# S1.net
KiCad netlist of a schematic drawn in EasyEDA Pro
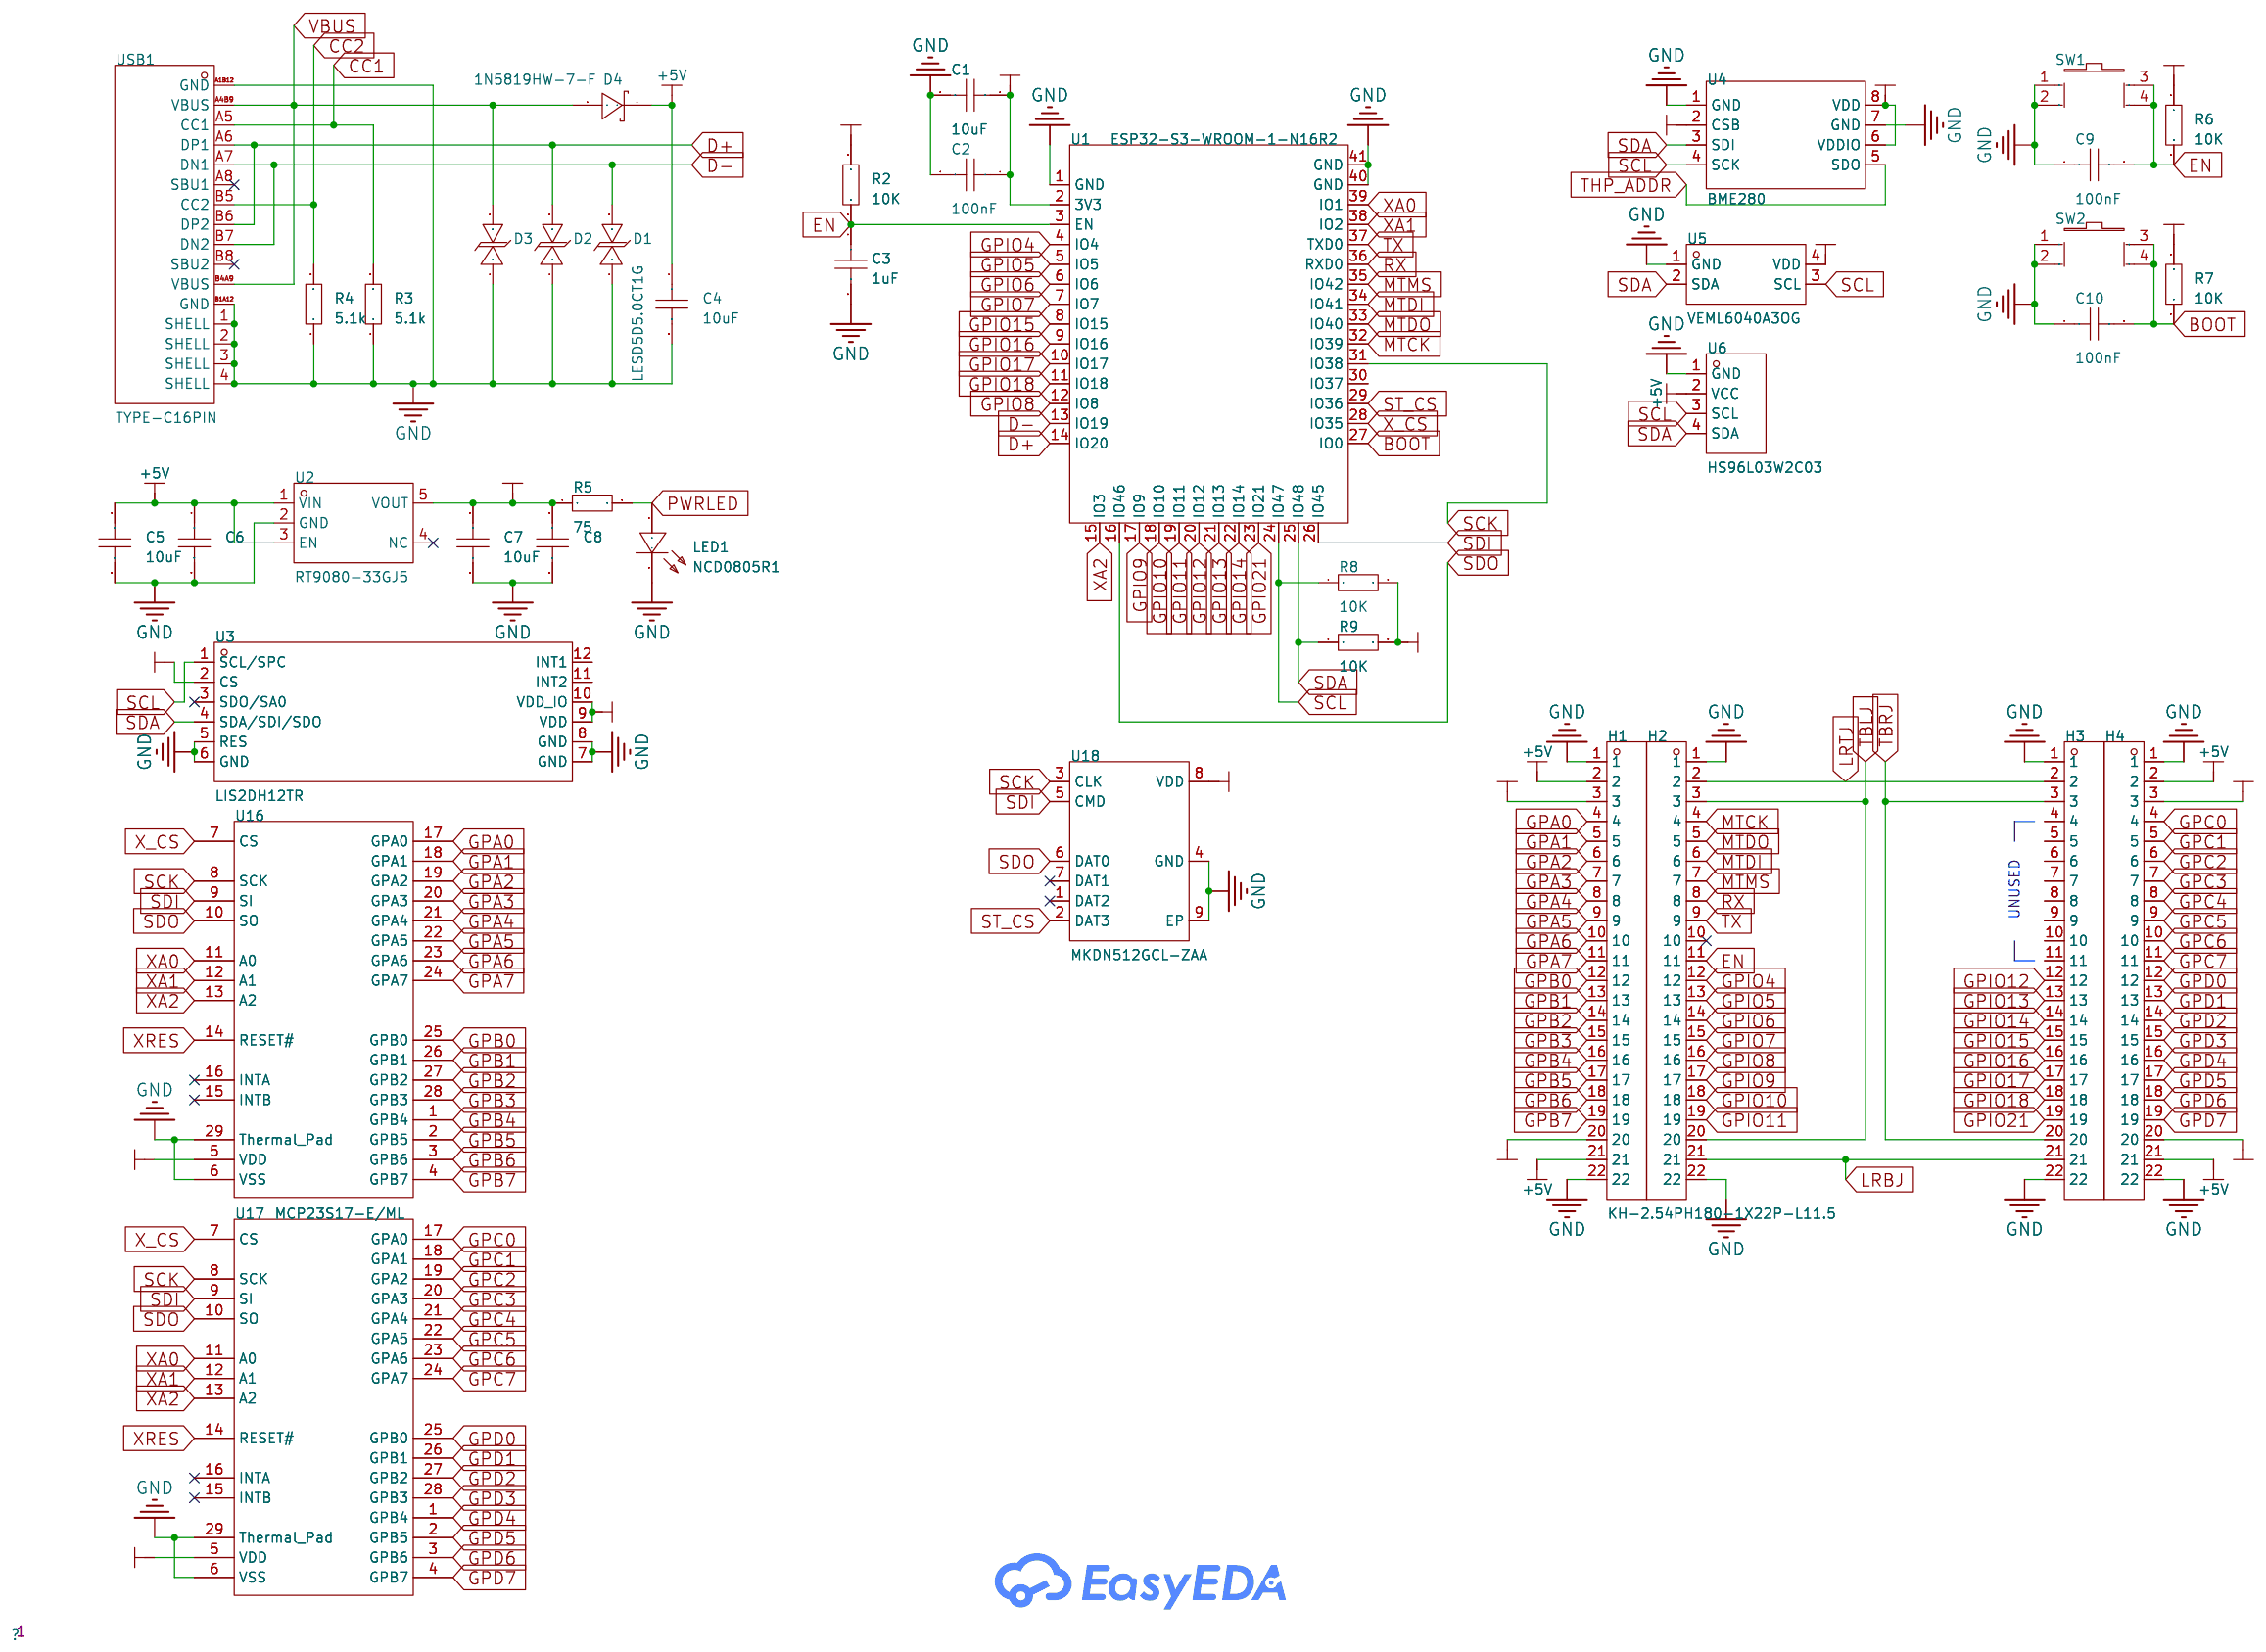
[diagram p0: schematic sheet]

(export (version "E")
  (design (tool "Eeschema 10.0.6"))
  (components
    (comp (ref "C1")
      (value "10uF")
      (footprint "easyedapro:C0603")
      (libsource (lib "easyedapro") (part "CAP"))
    )
    (comp (ref "C2")
      (value "100nF")
      (footprint "easyedapro:C0603")
      (libsource (lib "easyedapro") (part "CAP"))
    )
    (comp (ref "C3") (value "1uF") (footprint "easyedapro:C0603") (libsource (lib "easyedapro") (part "CAP")))
    (comp (ref "C4")
      (value "10uF")
      (footprint "easyedapro:C0603")
      (libsource (lib "easyedapro") (part "CAP"))
    )
    (comp (ref "C5")
      (value "10uF")
      (footprint "easyedapro:C0603")
      (libsource (lib "easyedapro") (part "CAP"))
    )
    (comp (ref "C6")
      (value "100nF")
      (footprint "easyedapro:C0603")
      (libsource (lib "easyedapro") (part "CAP"))
    )
    (comp (ref "C7")
      (value "10uF")
      (footprint "easyedapro:C0603")
      (libsource (lib "easyedapro") (part "CAP"))
    )
    (comp (ref "C8")
      (value "100nF")
      (footprint "easyedapro:C0603")
      (libsource (lib "easyedapro") (part "CAP"))
    )
    (comp (ref "C9")
      (value "100nF")
      (footprint "easyedapro:C0603")
      (libsource (lib "easyedapro") (part "CAP"))
    )
    (comp (ref "C10")
      (value "100nF")
      (footprint "easyedapro:C0603")
      (libsource (lib "easyedapro") (part "CAP"))
    )
    (comp (ref "D1")
      (value "LESD5D5.0CT1G")
      (footprint "easyedapro:SOD-523_L1.2-W0.8-LS1.6-BI")
      (fields (field (name "Manufacturer") "UMW(友台半导体)"))
      (libsource (lib "easyedapro") (part "LESD5D5.0CT1G_C5199850"))
    )
    (comp (ref "D2")
      (value "LESD5D5.0CT1G")
      (footprint "easyedapro:SOD-523_L1.2-W0.8-LS1.6-BI")
      (fields (field (name "Manufacturer") "UMW(友台半导体)"))
      (libsource (lib "easyedapro") (part "LESD5D5.0CT1G_C5199850"))
    )
    (comp (ref "D3")
      (value "LESD5D5.0CT1G")
      (footprint "easyedapro:SOD-523_L1.2-W0.8-LS1.6-BI")
      (fields (field (name "Manufacturer") "UMW(友台半导体)"))
      (libsource (lib "easyedapro") (part "LESD5D5.0CT1G_C5199850"))
    )
    (comp (ref "D4")
      (value "1N5819HW-7-F")
      (footprint "easyedapro:SOD-123_L2.7-W1.6-LS3.7-RD")
      (fields (field (name "Manufacturer") "DIODES(美台)"))
      (libsource (lib "easyedapro") (part "1N5819HW-7-F"))
    )
    (comp (ref "H1")
      (value "KH-2.54PH180-1X22P-L11.5")
      (footprint "easyedapro:HDR-TH_22P-P2.54-V-M")
      (description "Pin Structure:1x22P Pitch:2.54mm Number of Rows:Single Row")
      (fields (field (name "Manufacturer") "kinghelm(金航标)"))
      (libsource (lib "easyedapro") (part "KH-2.54PH180-1X22P-L11.5"))
    )
    (comp (ref "H2")
      (value "KH-2.54PH180-1X22P-L11.5")
      (footprint "easyedapro:HDR-TH_22P-P2.54-V-M")
      (description "Pin Structure:1x22P Pitch:2.54mm Number of Rows:Single Row")
      (fields (field (name "Manufacturer") "kinghelm(金航标)"))
      (libsource (lib "easyedapro") (part "KH-2.54PH180-1X22P-L11.5"))
    )
    (comp (ref "H3")
      (value "KH-2.54PH180-1X22P-L11.5")
      (footprint "easyedapro:HDR-TH_22P-P2.54-V-M")
      (description "Pin Structure:1x22P Pitch:2.54mm Number of Rows:Single Row")
      (fields (field (name "Manufacturer") "kinghelm(金航标)"))
      (libsource (lib "easyedapro") (part "KH-2.54PH180-1X22P-L11.5"))
    )
    (comp (ref "H4")
      (value "KH-2.54PH180-1X22P-L11.5")
      (footprint "easyedapro:HDR-TH_22P-P2.54-V-M")
      (description "Pin Structure:1x22P Pitch:2.54mm Number of Rows:Single Row")
      (fields (field (name "Manufacturer") "kinghelm(金航标)"))
      (libsource (lib "easyedapro") (part "KH-2.54PH180-1X22P-L11.5"))
    )
    (comp (ref "LED1")
      (value "NCD0805R1")
      (footprint "easyedapro:LED0805-R-RD")
      (fields (field (name "Manufacturer") "国星光电"))
      (libsource (lib "easyedapro") (part "FC-2012HRK-620D"))
    )
    (comp (ref "R2") (value "10K") (footprint "easyedapro:R0603") (libsource (lib "easyedapro") (part "Res")))
    (comp (ref "R3")
      (value "5.1k")
      (footprint "easyedapro:R0603")
      (libsource (lib "easyedapro") (part "Res"))
    )
    (comp (ref "R4")
      (value "5.1k")
      (footprint "easyedapro:R0603")
      (libsource (lib "easyedapro") (part "Res"))
    )
    (comp (ref "R5") (value "75") (footprint "easyedapro:R0603") (libsource (lib "easyedapro") (part "Res")))
    (comp (ref "R6") (value "10K") (footprint "easyedapro:R0603") (libsource (lib "easyedapro") (part "Res")))
    (comp (ref "R7") (value "10K") (footprint "easyedapro:R0603") (libsource (lib "easyedapro") (part "Res")))
    (comp (ref "R8") (value "10K") (footprint "easyedapro:R0603") (libsource (lib "easyedapro") (part "Res")))
    (comp (ref "R9") (value "10K") (footprint "easyedapro:R0603") (libsource (lib "easyedapro") (part "Res")))
    (comp (ref "SW1")
      (value "PTS810SJG250SMTRLFS")
      (footprint "easyedapro:SW-SMD_4P_PTS810SJM250SMTRLFS")
      (fields (field (name "Manufacturer") "C&K"))
      (libsource (lib "easyedapro") (part "PTS810SJG250SMTRLFS"))
    )
    (comp (ref "SW2")
      (value "PTS810SJG250SMTRLFS")
      (footprint "easyedapro:SW-SMD_4P_PTS810SJM250SMTRLFS")
      (fields (field (name "Manufacturer") "C&K"))
      (libsource (lib "easyedapro") (part "PTS810SJG250SMTRLFS"))
    )
    (comp (ref "U1")
      (value "ESP32-S3-WROOM-1-N16R2")
      (footprint "easyedapro:WIRELM-SMD_ESP32-S3-WROOM-1")
      (fields (field (name "Manufacturer") "ESPRESSIF(乐鑫)"))
      (libsource (lib "easyedapro") (part "ESP32-S3-WROOM-1(N16R2)"))
    )
    (comp (ref "U2")
      (value "RT9080-33GJ5")
      (footprint "easyedapro:TSOT-23-5_L2.9-W1.6-P0.95-LS2.8-BL")
      (description "+3V3")
      (fields (field (name "Manufacturer") "RICHTEK(立锜)"))
      (libsource (lib "easyedapro") (part "RT9080-33GJ5"))
    )
    (comp (ref "U3")
      (value "LIS2DH12TR")
      (footprint "easyedapro:LGA-12_L2.0-W2.0-P0.50-BL")
      (fields (field (name "Manufacturer") "ST(意法半导体)"))
      (libsource (lib "easyedapro") (part "LIS2DH12TR"))
    )
    (comp (ref "U4")
      (value "BME280")
      (footprint "easyedapro:LGA-8_BME280_BL")
      (description "Voltage - Supply:1.71V~3.6V Voltage - Supply:1.71V~3.6V")
      (fields (field (name "Manufacturer") "Bosch(博世)"))
      (libsource (lib "easyedapro") (part "BME280"))
    )
    (comp (ref "U5")
      (value "VEML6040A3OG")
      (footprint "easyedapro:SENSOR_SMD_VEML6040A3OG")
      (fields (field (name "Manufacturer") "VISHAY(威世)"))
      (libsource (lib "easyedapro") (part "VEML6040A3OG"))
    )
    (comp (ref "U6")
      (value "HS96L03W2C03")
      (footprint "easyedapro:OLED-TH_L27.8-W27.2-P2.54_C9900033791")
      (fields (field (name "Manufacturer") "HS(汉昇)"))
      (libsource (lib "easyedapro") (part "HS96L03W2C03"))
    )
    (comp (ref "U16")
      (value "MCP23S17-E/ML")
      (footprint "easyedapro:QFN-28_L6.0-W6.0-P0.65-BL-EP")
      (fields (field (name "Manufacturer") "MICROCHIP(美国微芯)"))
      (libsource (lib "easyedapro") (part "MCP23S17-E/ML"))
    )
    (comp (ref "U17")
      (value "MCP23S17-E/ML")
      (footprint "easyedapro:QFN-28_L6.0-W6.0-P0.65-BL-EP")
      (fields (field (name "Manufacturer") "MICROCHIP(美国微芯)"))
      (libsource (lib "easyedapro") (part "MCP23S17-E/ML"))
    )
    (comp (ref "U18")
      (value "MKDN512GCL-ZAA")
      (footprint "easyedapro:LGA-16_L12.5-W9.0-P1.27-TL-EP")
      (fields (field (name "Manufacturer") "MK(米客方德)"))
      (libsource (lib "easyedapro") (part "MKDN512GCL-ZAA"))
    )
    (comp (ref "USB1")
      (value "TYPE-C16PIN")
      (footprint "easyedapro:USB-C-SMD_TYPE-C16PIN")
      (fields (field (name "Manufacturer") "SHOU HAN(首韩)"))
      (libsource (lib "easyedapro") (part "TYPE-C16PIN"))
    )
  )
  (nets
    (net (code "1") (name "+3V3") (class "Default")
      (node (ref "C1") (pin "1") (pinfunction "1_1") (pintype "input"))
      (node (ref "C2") (pin "1") (pinfunction "1_1") (pintype "input"))
      (node (ref "C7") (pin "1") (pinfunction "1_1") (pintype "input"))
      (node (ref "C8") (pin "1") (pinfunction "1_1") (pintype "input"))
      (node (ref "H1") (pin "20") (pinfunction "20_20") (pintype "unspecified"))
      (node (ref "H1") (pin "3") (pinfunction "3_3") (pintype "unspecified"))
      (node (ref "H4") (pin "20") (pinfunction "20_20") (pintype "unspecified"))
      (node (ref "H4") (pin "3") (pinfunction "3_3") (pintype "unspecified"))
      (node (ref "R2") (pin "2") (pinfunction "2_2") (pintype "input"))
      (node (ref "R5") (pin "1") (pinfunction "1_1") (pintype "input"))
      (node (ref "R6") (pin "1") (pinfunction "1_1") (pintype "input"))
      (node (ref "R7") (pin "2") (pinfunction "2_2") (pintype "input"))
      (node (ref "R8") (pin "2") (pinfunction "2_2") (pintype "input"))
      (node (ref "R9") (pin "2") (pinfunction "2_2") (pintype "input"))
      (node (ref "U1") (pin "2") (pinfunction "3V3_2") (pintype "unspecified"))
      (node (ref "U16") (pin "5") (pinfunction "VDD_5") (pintype "input"))
      (node (ref "U17") (pin "5") (pinfunction "VDD_5") (pintype "input"))
      (node (ref "U18") (pin "8") (pinfunction "VDD_8") (pintype "unspecified"))
      (node (ref "U2") (pin "5") (pinfunction "VOUT_5") (pintype "unspecified"))
      (node (ref "U3") (pin "10") (pinfunction "VDD_IO_10") (pintype "unspecified"))
      (node (ref "U3") (pin "2") (pinfunction "CS_2") (pintype "unspecified"))
      (node (ref "U3") (pin "9") (pinfunction "VDD_9") (pintype "unspecified"))
      (node (ref "U4") (pin "2") (pinfunction "CSB_2") (pintype "unspecified"))
      (node (ref "U4") (pin "6") (pinfunction "VDDIO_6") (pintype "unspecified"))
      (node (ref "U4") (pin "8") (pinfunction "VDD_8") (pintype "unspecified"))
      (node (ref "U5") (pin "4") (pinfunction "VDD_4") (pintype "unspecified"))
    )
    (net (code "2") (name "+5V") (class "Default")
      (node (ref "C4") (pin "1") (pinfunction "1_1") (pintype "input"))
      (node (ref "C5") (pin "1") (pinfunction "1_1") (pintype "input"))
      (node (ref "C6") (pin "1") (pinfunction "1_1") (pintype "input"))
      (node (ref "D4") (pin "1") (pinfunction "K_1") (pintype "unspecified"))
      (node (ref "H1") (pin "2") (pinfunction "2_2") (pintype "unspecified"))
      (node (ref "H1") (pin "21") (pinfunction "21_21") (pintype "unspecified"))
      (node (ref "H4") (pin "2") (pinfunction "2_2") (pintype "unspecified"))
      (node (ref "H4") (pin "21") (pinfunction "21_21") (pintype "unspecified"))
      (node (ref "U2") (pin "1") (pinfunction "VIN_1") (pintype "unspecified"))
      (node (ref "U2") (pin "3") (pinfunction "EN_3") (pintype "unspecified"))
      (node (ref "U6") (pin "2") (pinfunction "VCC_2") (pintype "unspecified"))
    )
    (net (code "3") (name "BOOT") (class "Default")
      (node (ref "C10") (pin "2") (pinfunction "2_2") (pintype "input"))
      (node (ref "R7") (pin "1") (pinfunction "1_1") (pintype "input"))
      (node (ref "SW2") (pin "3") (pinfunction "3_3") (pintype "input"))
      (node (ref "SW2") (pin "4") (pinfunction "4_4") (pintype "input"))
      (node (ref "U1") (pin "27") (pinfunction "IO0_27") (pintype "unspecified"))
    )
    (net (code "4") (name "CC1") (class "Default")
      (node (ref "R3") (pin "2") (pinfunction "2_2") (pintype "input"))
      (node (ref "USB1") (pin "A5") (pinfunction "CC1_A5") (pintype "unspecified"))
    )
    (net (code "5") (name "CC2") (class "Default")
      (node (ref "R4") (pin "2") (pinfunction "2_2") (pintype "input"))
      (node (ref "USB1") (pin "B5") (pinfunction "CC2_B5") (pintype "unspecified"))
    )
    (net (code "6") (name "D+") (class "Default")
      (node (ref "D2") (pin "2") (pinfunction "2_2") (pintype "unspecified"))
      (node (ref "U1") (pin "14") (pinfunction "IO20_14") (pintype "unspecified"))
      (node (ref "USB1") (pin "A6") (pinfunction "DP1_A6") (pintype "unspecified"))
      (node (ref "USB1") (pin "B6") (pinfunction "DP2_B6") (pintype "unspecified"))
    )
    (net (code "7") (name "D-") (class "Default")
      (node (ref "D1") (pin "2") (pinfunction "2_2") (pintype "unspecified"))
      (node (ref "U1") (pin "13") (pinfunction "IO19_13") (pintype "unspecified"))
      (node (ref "USB1") (pin "A7") (pinfunction "DN1_A7") (pintype "unspecified"))
      (node (ref "USB1") (pin "B7") (pinfunction "DN2_B7") (pintype "unspecified"))
    )
    (net (code "8") (name "EN") (class "Default")
      (node (ref "C3") (pin "1") (pinfunction "1_1") (pintype "input"))
      (node (ref "C9") (pin "2") (pinfunction "2_2") (pintype "input"))
      (node (ref "H2") (pin "11") (pinfunction "11_11") (pintype "unspecified"))
      (node (ref "R2") (pin "1") (pinfunction "1_1") (pintype "input"))
      (node (ref "R6") (pin "2") (pinfunction "2_2") (pintype "input"))
      (node (ref "SW1") (pin "3") (pinfunction "3_3") (pintype "input"))
      (node (ref "SW1") (pin "4") (pinfunction "4_4") (pintype "input"))
      (node (ref "U1") (pin "3") (pinfunction "EN_3") (pintype "unspecified"))
    )
    (net (code "9") (name "GND") (class "Default")
      (node (ref "C1") (pin "2") (pinfunction "2_2") (pintype "input"))
      (node (ref "C10") (pin "1") (pinfunction "1_1") (pintype "input"))
      (node (ref "C2") (pin "2") (pinfunction "2_2") (pintype "input"))
      (node (ref "C3") (pin "2") (pinfunction "2_2") (pintype "input"))
      (node (ref "C4") (pin "2") (pinfunction "2_2") (pintype "input"))
      (node (ref "C5") (pin "2") (pinfunction "2_2") (pintype "input"))
      (node (ref "C6") (pin "2") (pinfunction "2_2") (pintype "input"))
      (node (ref "C7") (pin "2") (pinfunction "2_2") (pintype "input"))
      (node (ref "C8") (pin "2") (pinfunction "2_2") (pintype "input"))
      (node (ref "C9") (pin "1") (pinfunction "1_1") (pintype "input"))
      (node (ref "D1") (pin "1") (pinfunction "1_1") (pintype "unspecified"))
      (node (ref "D2") (pin "1") (pinfunction "1_1") (pintype "unspecified"))
      (node (ref "D3") (pin "1") (pinfunction "1_1") (pintype "unspecified"))
      (node (ref "H1") (pin "1") (pinfunction "1_1") (pintype "unspecified"))
      (node (ref "H1") (pin "22") (pinfunction "22_22") (pintype "unspecified"))
      (node (ref "H2") (pin "1") (pinfunction "1_1") (pintype "unspecified"))
      (node (ref "H2") (pin "22") (pinfunction "22_22") (pintype "unspecified"))
      (node (ref "H3") (pin "1") (pinfunction "1_1") (pintype "unspecified"))
      (node (ref "H3") (pin "22") (pinfunction "22_22") (pintype "unspecified"))
      (node (ref "H4") (pin "1") (pinfunction "1_1") (pintype "unspecified"))
      (node (ref "H4") (pin "22") (pinfunction "22_22") (pintype "unspecified"))
      (node (ref "LED1") (pin "2") (pinfunction "-_2") (pintype "unspecified"))
      (node (ref "R3") (pin "1") (pinfunction "1_1") (pintype "input"))
      (node (ref "R4") (pin "1") (pinfunction "1_1") (pintype "input"))
      (node (ref "SW1") (pin "1") (pinfunction "1_1") (pintype "input"))
      (node (ref "SW1") (pin "2") (pinfunction "2_2") (pintype "input"))
      (node (ref "SW2") (pin "1") (pinfunction "1_1") (pintype "input"))
      (node (ref "SW2") (pin "2") (pinfunction "2_2") (pintype "input"))
      (node (ref "U1") (pin "1") (pinfunction "GND_1") (pintype "unspecified"))
      (node (ref "U1") (pin "40") (pinfunction "GND_40") (pintype "unspecified"))
      (node (ref "U1") (pin "41") (pinfunction "GND_41") (pintype "unspecified"))
      (node (ref "U16") (pin "29") (pinfunction "Thermal_Pad_29") (pintype "input"))
      (node (ref "U16") (pin "6") (pinfunction "VSS_6") (pintype "input"))
      (node (ref "U17") (pin "29") (pinfunction "Thermal_Pad_29") (pintype "input"))
      (node (ref "U17") (pin "6") (pinfunction "VSS_6") (pintype "input"))
      (node (ref "U18") (pin "4") (pinfunction "GND_4") (pintype "unspecified"))
      (node (ref "U18") (pin "9") (pinfunction "EP_9") (pintype "unspecified"))
      (node (ref "U2") (pin "2") (pinfunction "GND_2") (pintype "unspecified"))
      (node (ref "U3") (pin "5") (pinfunction "RES_5") (pintype "unspecified"))
      (node (ref "U3") (pin "6") (pinfunction "GND_6") (pintype "unspecified"))
      (node (ref "U3") (pin "7") (pinfunction "GND_7") (pintype "unspecified"))
      (node (ref "U3") (pin "8") (pinfunction "GND_8") (pintype "unspecified"))
      (node (ref "U4") (pin "1") (pinfunction "GND_1") (pintype "unspecified"))
      (node (ref "U4") (pin "7") (pinfunction "GND_7") (pintype "unspecified"))
      (node (ref "U5") (pin "1") (pinfunction "GND_1") (pintype "unspecified"))
      (node (ref "U6") (pin "1") (pinfunction "GND_1") (pintype "unspecified"))
      (node (ref "USB1") (pin "1") (pinfunction "SHELL_1") (pintype "unspecified"))
      (node (ref "USB1") (pin "2") (pinfunction "SHELL_2") (pintype "unspecified"))
      (node (ref "USB1") (pin "3") (pinfunction "SHELL_3") (pintype "unspecified"))
      (node (ref "USB1") (pin "4") (pinfunction "SHELL_4") (pintype "unspecified"))
      (node (ref "USB1") (pin "A1B12") (pinfunction "GND_A1B12") (pintype "unspecified"))
      (node (ref "USB1") (pin "B1A12") (pinfunction "GND_B1A12") (pintype "unspecified"))
    )
    (net (code "10") (name "GPA0") (class "Default")
      (node (ref "H1") (pin "4") (pinfunction "4_4") (pintype "unspecified"))
      (node (ref "U16") (pin "17") (pinfunction "GPA0_17") (pintype "bidirectional"))
    )
    (net (code "11") (name "GPA1") (class "Default")
      (node (ref "H1") (pin "5") (pinfunction "5_5") (pintype "unspecified"))
      (node (ref "U16") (pin "18") (pinfunction "GPA1_18") (pintype "bidirectional"))
    )
    (net (code "12") (name "GPA2") (class "Default")
      (node (ref "H1") (pin "6") (pinfunction "6_6") (pintype "unspecified"))
      (node (ref "U16") (pin "19") (pinfunction "GPA2_19") (pintype "bidirectional"))
    )
    (net (code "13") (name "GPA3") (class "Default")
      (node (ref "H1") (pin "7") (pinfunction "7_7") (pintype "unspecified"))
      (node (ref "U16") (pin "20") (pinfunction "GPA3_20") (pintype "bidirectional"))
    )
    (net (code "14") (name "GPA4") (class "Default")
      (node (ref "H1") (pin "8") (pinfunction "8_8") (pintype "unspecified"))
      (node (ref "U16") (pin "21") (pinfunction "GPA4_21") (pintype "bidirectional"))
    )
    (net (code "15") (name "GPA5") (class "Default")
      (node (ref "H1") (pin "9") (pinfunction "9_9") (pintype "unspecified"))
      (node (ref "U16") (pin "22") (pinfunction "GPA5_22") (pintype "bidirectional"))
    )
    (net (code "16") (name "GPA6") (class "Default")
      (node (ref "H1") (pin "10") (pinfunction "10_10") (pintype "unspecified"))
      (node (ref "U16") (pin "23") (pinfunction "GPA6_23") (pintype "bidirectional"))
    )
    (net (code "17") (name "GPA7") (class "Default")
      (node (ref "H1") (pin "11") (pinfunction "11_11") (pintype "unspecified"))
      (node (ref "U16") (pin "24") (pinfunction "GPA7_24") (pintype "bidirectional"))
    )
    (net (code "18") (name "GPB0") (class "Default")
      (node (ref "H1") (pin "12") (pinfunction "12_12") (pintype "unspecified"))
      (node (ref "U16") (pin "25") (pinfunction "GPB0_25") (pintype "bidirectional"))
    )
    (net (code "19") (name "GPB1") (class "Default")
      (node (ref "H1") (pin "13") (pinfunction "13_13") (pintype "unspecified"))
      (node (ref "U16") (pin "26") (pinfunction "GPB1_26") (pintype "bidirectional"))
    )
    (net (code "20") (name "GPB2") (class "Default")
      (node (ref "H1") (pin "14") (pinfunction "14_14") (pintype "unspecified"))
      (node (ref "U16") (pin "27") (pinfunction "GPB2_27") (pintype "bidirectional"))
    )
    (net (code "21") (name "GPB3") (class "Default")
      (node (ref "H1") (pin "15") (pinfunction "15_15") (pintype "unspecified"))
      (node (ref "U16") (pin "28") (pinfunction "GPB3_28") (pintype "bidirectional"))
    )
    (net (code "22") (name "GPB4") (class "Default")
      (node (ref "H1") (pin "16") (pinfunction "16_16") (pintype "unspecified"))
      (node (ref "U16") (pin "1") (pinfunction "GPB4_1") (pintype "bidirectional"))
    )
    (net (code "23") (name "GPB5") (class "Default")
      (node (ref "H1") (pin "17") (pinfunction "17_17") (pintype "unspecified"))
      (node (ref "U16") (pin "2") (pinfunction "GPB5_2") (pintype "bidirectional"))
    )
    (net (code "24") (name "GPB6") (class "Default")
      (node (ref "H1") (pin "18") (pinfunction "18_18") (pintype "unspecified"))
      (node (ref "U16") (pin "3") (pinfunction "GPB6_3") (pintype "bidirectional"))
    )
    (net (code "25") (name "GPB7") (class "Default")
      (node (ref "H1") (pin "19") (pinfunction "19_19") (pintype "unspecified"))
      (node (ref "U16") (pin "4") (pinfunction "GPB7_4") (pintype "bidirectional"))
    )
    (net (code "26") (name "GPC0") (class "Default")
      (node (ref "H4") (pin "4") (pinfunction "4_4") (pintype "unspecified"))
      (node (ref "U17") (pin "17") (pinfunction "GPA0_17") (pintype "bidirectional"))
    )
    (net (code "27") (name "GPC1") (class "Default")
      (node (ref "H4") (pin "5") (pinfunction "5_5") (pintype "unspecified"))
      (node (ref "U17") (pin "18") (pinfunction "GPA1_18") (pintype "bidirectional"))
    )
    (net (code "28") (name "GPC2") (class "Default")
      (node (ref "H4") (pin "6") (pinfunction "6_6") (pintype "unspecified"))
      (node (ref "U17") (pin "19") (pinfunction "GPA2_19") (pintype "bidirectional"))
    )
    (net (code "29") (name "GPC3") (class "Default")
      (node (ref "H4") (pin "7") (pinfunction "7_7") (pintype "unspecified"))
      (node (ref "U17") (pin "20") (pinfunction "GPA3_20") (pintype "bidirectional"))
    )
    (net (code "30") (name "GPC4") (class "Default")
      (node (ref "H4") (pin "8") (pinfunction "8_8") (pintype "unspecified"))
      (node (ref "U17") (pin "21") (pinfunction "GPA4_21") (pintype "bidirectional"))
    )
    (net (code "31") (name "GPC5") (class "Default")
      (node (ref "H4") (pin "9") (pinfunction "9_9") (pintype "unspecified"))
      (node (ref "U17") (pin "22") (pinfunction "GPA5_22") (pintype "bidirectional"))
    )
    (net (code "32") (name "GPC6") (class "Default")
      (node (ref "H4") (pin "10") (pinfunction "10_10") (pintype "unspecified"))
      (node (ref "U17") (pin "23") (pinfunction "GPA6_23") (pintype "bidirectional"))
    )
    (net (code "33") (name "GPC7") (class "Default")
      (node (ref "H4") (pin "11") (pinfunction "11_11") (pintype "unspecified"))
      (node (ref "U17") (pin "24") (pinfunction "GPA7_24") (pintype "bidirectional"))
    )
    (net (code "34") (name "GPD0") (class "Default")
      (node (ref "H4") (pin "12") (pinfunction "12_12") (pintype "unspecified"))
      (node (ref "U17") (pin "25") (pinfunction "GPB0_25") (pintype "bidirectional"))
    )
    (net (code "35") (name "GPD1") (class "Default")
      (node (ref "H4") (pin "13") (pinfunction "13_13") (pintype "unspecified"))
      (node (ref "U17") (pin "26") (pinfunction "GPB1_26") (pintype "bidirectional"))
    )
    (net (code "36") (name "GPD2") (class "Default")
      (node (ref "H4") (pin "14") (pinfunction "14_14") (pintype "unspecified"))
      (node (ref "U17") (pin "27") (pinfunction "GPB2_27") (pintype "bidirectional"))
    )
    (net (code "37") (name "GPD3") (class "Default")
      (node (ref "H4") (pin "15") (pinfunction "15_15") (pintype "unspecified"))
      (node (ref "U17") (pin "28") (pinfunction "GPB3_28") (pintype "bidirectional"))
    )
    (net (code "38") (name "GPD4") (class "Default")
      (node (ref "H4") (pin "16") (pinfunction "16_16") (pintype "unspecified"))
      (node (ref "U17") (pin "1") (pinfunction "GPB4_1") (pintype "bidirectional"))
    )
    (net (code "39") (name "GPD5") (class "Default")
      (node (ref "H4") (pin "17") (pinfunction "17_17") (pintype "unspecified"))
      (node (ref "U17") (pin "2") (pinfunction "GPB5_2") (pintype "bidirectional"))
    )
    (net (code "40") (name "GPD6") (class "Default")
      (node (ref "H4") (pin "18") (pinfunction "18_18") (pintype "unspecified"))
      (node (ref "U17") (pin "3") (pinfunction "GPB6_3") (pintype "bidirectional"))
    )
    (net (code "41") (name "GPD7") (class "Default")
      (node (ref "H4") (pin "19") (pinfunction "19_19") (pintype "unspecified"))
      (node (ref "U17") (pin "4") (pinfunction "GPB7_4") (pintype "bidirectional"))
    )
    (net (code "42") (name "GPIO4") (class "Default")
      (node (ref "H2") (pin "12") (pinfunction "12_12") (pintype "unspecified"))
      (node (ref "U1") (pin "4") (pinfunction "IO4_4") (pintype "unspecified"))
    )
    (net (code "43") (name "GPIO5") (class "Default")
      (node (ref "H2") (pin "13") (pinfunction "13_13") (pintype "unspecified"))
      (node (ref "U1") (pin "5") (pinfunction "IO5_5") (pintype "unspecified"))
    )
    (net (code "44") (name "GPIO6") (class "Default")
      (node (ref "H2") (pin "14") (pinfunction "14_14") (pintype "unspecified"))
      (node (ref "U1") (pin "6") (pinfunction "IO6_6") (pintype "unspecified"))
    )
    (net (code "45") (name "GPIO7") (class "Default")
      (node (ref "H2") (pin "15") (pinfunction "15_15") (pintype "unspecified"))
      (node (ref "U1") (pin "7") (pinfunction "IO7_7") (pintype "unspecified"))
    )
    (net (code "46") (name "GPIO8") (class "Default")
      (node (ref "H2") (pin "16") (pinfunction "16_16") (pintype "unspecified"))
      (node (ref "U1") (pin "12") (pinfunction "IO8_12") (pintype "unspecified"))
    )
    (net (code "47") (name "GPIO9") (class "Default")
      (node (ref "H2") (pin "17") (pinfunction "17_17") (pintype "unspecified"))
      (node (ref "U1") (pin "17") (pinfunction "IO9_17") (pintype "unspecified"))
    )
    (net (code "48") (name "GPIO10") (class "Default")
      (node (ref "H2") (pin "18") (pinfunction "18_18") (pintype "unspecified"))
      (node (ref "U1") (pin "18") (pinfunction "IO10_18") (pintype "unspecified"))
    )
    (net (code "49") (name "GPIO11") (class "Default")
      (node (ref "H2") (pin "19") (pinfunction "19_19") (pintype "unspecified"))
      (node (ref "U1") (pin "19") (pinfunction "IO11_19") (pintype "unspecified"))
    )
    (net (code "50") (name "GPIO12") (class "Default")
      (node (ref "H3") (pin "12") (pinfunction "12_12") (pintype "unspecified"))
      (node (ref "U1") (pin "20") (pinfunction "IO12_20") (pintype "unspecified"))
    )
    (net (code "51") (name "GPIO13") (class "Default")
      (node (ref "H3") (pin "13") (pinfunction "13_13") (pintype "unspecified"))
      (node (ref "U1") (pin "21") (pinfunction "IO13_21") (pintype "unspecified"))
    )
    (net (code "52") (name "GPIO14") (class "Default")
      (node (ref "H3") (pin "14") (pinfunction "14_14") (pintype "unspecified"))
      (node (ref "U1") (pin "22") (pinfunction "IO14_22") (pintype "unspecified"))
    )
    (net (code "53") (name "GPIO15") (class "Default")
      (node (ref "H3") (pin "15") (pinfunction "15_15") (pintype "unspecified"))
      (node (ref "U1") (pin "8") (pinfunction "IO15_8") (pintype "unspecified"))
    )
    (net (code "54") (name "GPIO16") (class "Default")
      (node (ref "H3") (pin "16") (pinfunction "16_16") (pintype "unspecified"))
      (node (ref "U1") (pin "9") (pinfunction "IO16_9") (pintype "unspecified"))
    )
    (net (code "55") (name "GPIO17") (class "Default")
      (node (ref "H3") (pin "17") (pinfunction "17_17") (pintype "unspecified"))
      (node (ref "U1") (pin "10") (pinfunction "IO17_10") (pintype "unspecified"))
    )
    (net (code "56") (name "GPIO18") (class "Default")
      (node (ref "H3") (pin "18") (pinfunction "18_18") (pintype "unspecified"))
      (node (ref "U1") (pin "11") (pinfunction "IO18_11") (pintype "unspecified"))
    )
    (net (code "57") (name "GPIO21") (class "Default")
      (node (ref "H3") (pin "19") (pinfunction "19_19") (pintype "unspecified"))
      (node (ref "U1") (pin "23") (pinfunction "IO21_23") (pintype "unspecified"))
    )
    (net (code "58") (name "LRBJ") (class "Default")
      (node (ref "H2") (pin "21") (pinfunction "21_21") (pintype "unspecified"))
      (node (ref "H3") (pin "21") (pinfunction "21_21") (pintype "unspecified"))
    )
    (net (code "59") (name "LRTJ") (class "Default")
      (node (ref "H2") (pin "2") (pinfunction "2_2") (pintype "unspecified"))
      (node (ref "H3") (pin "2") (pinfunction "2_2") (pintype "unspecified"))
    )
    (net (code "60") (name "MTCK") (class "Default")
      (node (ref "H2") (pin "4") (pinfunction "4_4") (pintype "unspecified"))
      (node (ref "U1") (pin "32") (pinfunction "IO39_32") (pintype "unspecified"))
    )
    (net (code "61") (name "MTDI") (class "Default")
      (node (ref "H2") (pin "6") (pinfunction "6_6") (pintype "unspecified"))
      (node (ref "U1") (pin "34") (pinfunction "IO41_34") (pintype "unspecified"))
    )
    (net (code "62") (name "MTDO") (class "Default")
      (node (ref "H2") (pin "5") (pinfunction "5_5") (pintype "unspecified"))
      (node (ref "U1") (pin "33") (pinfunction "IO40_33") (pintype "unspecified"))
    )
    (net (code "63") (name "MTMS") (class "Default")
      (node (ref "H2") (pin "7") (pinfunction "7_7") (pintype "unspecified"))
      (node (ref "U1") (pin "35") (pinfunction "IO42_35") (pintype "unspecified"))
    )
    (net (code "64") (name "PWRLED") (class "Default")
      (node (ref "LED1") (pin "1") (pinfunction "+_1") (pintype "unspecified"))
      (node (ref "R5") (pin "2") (pinfunction "2_2") (pintype "input"))
    )
    (net (code "65") (name "RX") (class "Default")
      (node (ref "H2") (pin "8") (pinfunction "8_8") (pintype "unspecified"))
      (node (ref "U1") (pin "36") (pinfunction "RXD0_36") (pintype "unspecified"))
    )
    (net (code "66") (name "SCK") (class "Default")
      (node (ref "U1") (pin "31") (pinfunction "IO38_31") (pintype "unspecified"))
      (node (ref "U16") (pin "8") (pinfunction "SCK_8") (pintype "input"))
      (node (ref "U17") (pin "8") (pinfunction "SCK_8") (pintype "input"))
      (node (ref "U18") (pin "3") (pinfunction "CLK_3") (pintype "unspecified"))
    )
    (net (code "67") (name "SCL") (class "Default")
      (node (ref "R8") (pin "1") (pinfunction "1_1") (pintype "input"))
      (node (ref "U1") (pin "24") (pinfunction "IO47_24") (pintype "unspecified"))
      (node (ref "U3") (pin "1") (pinfunction "SCL/SPC_1") (pintype "unspecified"))
      (node (ref "U4") (pin "4") (pinfunction "SCK_4") (pintype "unspecified"))
      (node (ref "U5") (pin "3") (pinfunction "SCL_3") (pintype "unspecified"))
      (node (ref "U6") (pin "3") (pinfunction "SCL_3") (pintype "unspecified"))
    )
    (net (code "68") (name "SDA") (class "Default")
      (node (ref "R9") (pin "1") (pinfunction "1_1") (pintype "input"))
      (node (ref "U1") (pin "25") (pinfunction "IO48_25") (pintype "unspecified"))
      (node (ref "U3") (pin "4") (pinfunction "SDA/SDI/SDO_4") (pintype "unspecified"))
      (node (ref "U4") (pin "3") (pinfunction "SDI_3") (pintype "unspecified"))
      (node (ref "U5") (pin "2") (pinfunction "SDA_2") (pintype "unspecified"))
      (node (ref "U6") (pin "4") (pinfunction "SDA_4") (pintype "unspecified"))
    )
    (net (code "69") (name "SDI") (class "Default")
      (node (ref "U1") (pin "26") (pinfunction "IO45_26") (pintype "unspecified"))
      (node (ref "U16") (pin "9") (pinfunction "SI_9") (pintype "input"))
      (node (ref "U17") (pin "9") (pinfunction "SI_9") (pintype "input"))
      (node (ref "U18") (pin "5") (pinfunction "CMD_5") (pintype "unspecified"))
    )
    (net (code "70") (name "SDO") (class "Default")
      (node (ref "U1") (pin "16") (pinfunction "IO46_16") (pintype "unspecified"))
      (node (ref "U16") (pin "10") (pinfunction "SO_10") (pintype "input"))
      (node (ref "U17") (pin "10") (pinfunction "SO_10") (pintype "input"))
      (node (ref "U18") (pin "6") (pinfunction "DAT0_6") (pintype "unspecified"))
    )
    (net (code "71") (name "ST_CS") (class "Default")
      (node (ref "U1") (pin "29") (pinfunction "IO36_29") (pintype "unspecified"))
      (node (ref "U18") (pin "2") (pinfunction "DAT3_2") (pintype "unspecified"))
    )
    (net (code "72") (name "TBLJ") (class "Default")
      (node (ref "H2") (pin "20") (pinfunction "20_20") (pintype "unspecified"))
      (node (ref "H2") (pin "3") (pinfunction "3_3") (pintype "unspecified"))
    )
    (net (code "73") (name "TBRJ") (class "Default")
      (node (ref "H3") (pin "20") (pinfunction "20_20") (pintype "unspecified"))
      (node (ref "H3") (pin "3") (pinfunction "3_3") (pintype "unspecified"))
    )
    (net (code "74") (name "THP_ADDR") (class "Default")
      (node (ref "U4") (pin "5") (pinfunction "SDO_5") (pintype "unspecified"))
    )
    (net (code "75") (name "TX") (class "Default")
      (node (ref "H2") (pin "9") (pinfunction "9_9") (pintype "unspecified"))
      (node (ref "U1") (pin "37") (pinfunction "TXD0_37") (pintype "unspecified"))
    )
    (net (code "76") (name "VBUS") (class "Default")
      (node (ref "D3") (pin "2") (pinfunction "2_2") (pintype "unspecified"))
      (node (ref "D4") (pin "2") (pinfunction "A_2") (pintype "unspecified"))
      (node (ref "USB1") (pin "A4B9") (pinfunction "VBUS_A4B9") (pintype "unspecified"))
      (node (ref "USB1") (pin "B4A9") (pinfunction "VBUS_B4A9") (pintype "unspecified"))
    )
    (net (code "77") (name "XA0") (class "Default")
      (node (ref "U1") (pin "39") (pinfunction "IO1_39") (pintype "unspecified"))
      (node (ref "U16") (pin "11") (pinfunction "A0_11") (pintype "input"))
      (node (ref "U17") (pin "11") (pinfunction "A0_11") (pintype "input"))
    )
    (net (code "78") (name "XA1") (class "Default")
      (node (ref "U1") (pin "38") (pinfunction "IO2_38") (pintype "unspecified"))
      (node (ref "U16") (pin "12") (pinfunction "A1_12") (pintype "input"))
      (node (ref "U17") (pin "12") (pinfunction "A1_12") (pintype "input"))
    )
    (net (code "79") (name "XA2") (class "Default")
      (node (ref "U1") (pin "15") (pinfunction "IO3_15") (pintype "unspecified"))
      (node (ref "U16") (pin "13") (pinfunction "A2_13") (pintype "input"))
      (node (ref "U17") (pin "13") (pinfunction "A2_13") (pintype "input"))
    )
    (net (code "80") (name "XRES") (class "Default")
      (node (ref "U16") (pin "14") (pinfunction "RESET#_14") (pintype "input"))
      (node (ref "U17") (pin "14") (pinfunction "RESET#_14") (pintype "input"))
    )
    (net (code "81") (name "X_CS") (class "Default")
      (node (ref "U1") (pin "28") (pinfunction "IO35_28") (pintype "unspecified"))
      (node (ref "U16") (pin "7") (pinfunction "CS_7") (pintype "input"))
      (node (ref "U17") (pin "7") (pinfunction "CS_7") (pintype "input"))
    )
    (net (code "82") (name "unconnected-(H2-Pad10)") (class "Default")
      (node (ref "H2") (pin "10") (pinfunction "10_10") (pintype "unspecified+no_connect"))
    )
    (net (code "83") (name "unconnected-(H3-Pad4)") (class "Default")
      (node (ref "H3") (pin "4") (pinfunction "4_4") (pintype "unspecified"))
    )
    (net (code "84") (name "unconnected-(H3-Pad5)") (class "Default")
      (node (ref "H3") (pin "5") (pinfunction "5_5") (pintype "unspecified"))
    )
    (net (code "85") (name "unconnected-(H3-Pad6)") (class "Default")
      (node (ref "H3") (pin "6") (pinfunction "6_6") (pintype "unspecified"))
    )
    (net (code "86") (name "unconnected-(H3-Pad7)") (class "Default")
      (node (ref "H3") (pin "7") (pinfunction "7_7") (pintype "unspecified"))
    )
    (net (code "87") (name "unconnected-(H3-Pad8)") (class "Default")
      (node (ref "H3") (pin "8") (pinfunction "8_8") (pintype "unspecified"))
    )
    (net (code "88") (name "unconnected-(H3-Pad9)") (class "Default")
      (node (ref "H3") (pin "9") (pinfunction "9_9") (pintype "unspecified"))
    )
    (net (code "89") (name "unconnected-(H3-Pad10)") (class "Default")
      (node (ref "H3") (pin "10") (pinfunction "10_10") (pintype "unspecified"))
    )
    (net (code "90") (name "unconnected-(H3-Pad11)") (class "Default")
      (node (ref "H3") (pin "11") (pinfunction "11_11") (pintype "unspecified"))
    )
    (net (code "91") (name "unconnected-(U1-IO37-Pad30)") (class "Default")
      (node (ref "U1") (pin "30") (pinfunction "IO37_30") (pintype "unspecified"))
    )
    (net (code "92") (name "unconnected-(U2-NC-Pad4)") (class "Default")
      (node (ref "U2") (pin "4") (pinfunction "NC_4") (pintype "unspecified+no_connect"))
    )
    (net (code "93") (name "unconnected-(U3-INT1-Pad12)") (class "Default")
      (node (ref "U3") (pin "12") (pinfunction "INT1_12") (pintype "unspecified"))
    )
    (net (code "94") (name "unconnected-(U3-INT2-Pad11)") (class "Default")
      (node (ref "U3") (pin "11") (pinfunction "INT2_11") (pintype "unspecified"))
    )
    (net (code "95") (name "unconnected-(U3-SDO{slash}SA0-Pad3)") (class "Default")
      (node (ref "U3") (pin "3") (pinfunction "SDO/SA0_3") (pintype "unspecified+no_connect"))
    )
    (net (code "96") (name "unconnected-(U16-INTA-Pad16)") (class "Default")
      (node (ref "U16") (pin "16") (pinfunction "INTA_16") (pintype "input+no_connect"))
    )
    (net (code "97") (name "unconnected-(U16-INTB-Pad15)") (class "Default")
      (node (ref "U16") (pin "15") (pinfunction "INTB_15") (pintype "input+no_connect"))
    )
    (net (code "98") (name "unconnected-(U17-INTA-Pad16)") (class "Default")
      (node (ref "U17") (pin "16") (pinfunction "INTA_16") (pintype "input+no_connect"))
    )
    (net (code "99") (name "unconnected-(U17-INTB-Pad15)") (class "Default")
      (node (ref "U17") (pin "15") (pinfunction "INTB_15") (pintype "input+no_connect"))
    )
    (net (code "100") (name "unconnected-(U18-DAT1-Pad7)") (class "Default")
      (node (ref "U18") (pin "7") (pinfunction "DAT1_7") (pintype "unspecified+no_connect"))
    )
    (net (code "101") (name "unconnected-(U18-DAT2-Pad1)") (class "Default")
      (node (ref "U18") (pin "1") (pinfunction "DAT2_1") (pintype "unspecified+no_connect"))
    )
    (net (code "102") (name "unconnected-(USB1-SBU1-PadA8)") (class "Default")
      (node (ref "USB1") (pin "A8") (pinfunction "SBU1_A8") (pintype "unspecified+no_connect"))
    )
    (net (code "103") (name "unconnected-(USB1-SBU2-PadB8)") (class "Default")
      (node (ref "USB1") (pin "B8") (pinfunction "SBU2_B8") (pintype "unspecified+no_connect"))
    )
  )
)
